# rev1_5.net
KiCad netlist of a schematic drawn in EAGLE
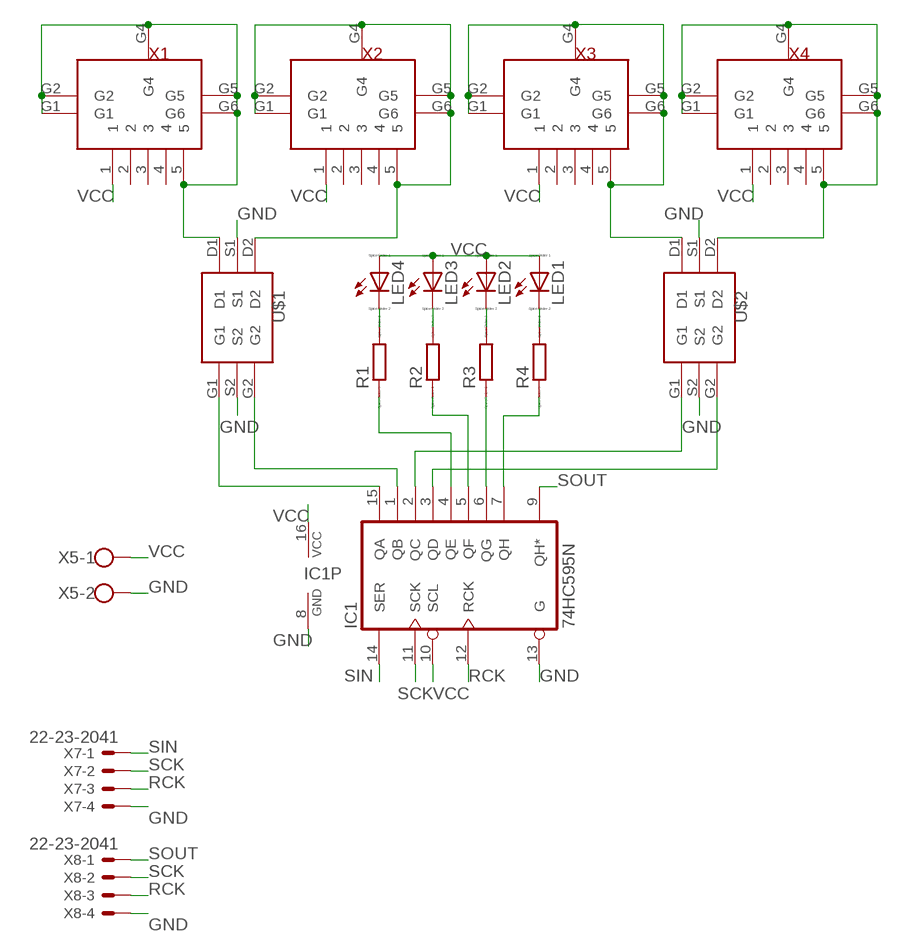
[diagram p0: schematic, sheet 1]

(export (version "E")
  (design (tool "Eeschema 10.0.6"))
  (components
    (comp (ref "IC1")
      (value "74HC595N")
      (footprint "eagle-import:DIL16")
      (libsource (lib "eagle-import") (part "74595NHC"))
    )
    (comp (ref "LED1")
      (value "LED_E")
      (footprint "eagle-import:LED_1206")
      (libsource (lib "eagle-import") (part "LED_E"))
    )
    (comp (ref "LED2")
      (value "LED_E")
      (footprint "eagle-import:LED_1206")
      (libsource (lib "eagle-import") (part "LED_E"))
    )
    (comp (ref "LED3")
      (value "LED_E")
      (footprint "eagle-import:LED_1206")
      (libsource (lib "eagle-import") (part "LED_E"))
    )
    (comp (ref "LED4")
      (value "LED_E")
      (footprint "eagle-import:LED_1206")
      (libsource (lib "eagle-import") (part "LED_E"))
    )
    (comp (ref "R1")
      (value "RR1005")
      (footprint "eagle-import:R1005")
      (libsource (lib "eagle-import") (part "RR1005"))
    )
    (comp (ref "R2")
      (value "RR1005")
      (footprint "eagle-import:R1005")
      (libsource (lib "eagle-import") (part "RR1005"))
    )
    (comp (ref "R3")
      (value "RR1005")
      (footprint "eagle-import:R1005")
      (libsource (lib "eagle-import") (part "RR1005"))
    )
    (comp (ref "R4")
      (value "RR1005")
      (footprint "eagle-import:R1005")
      (libsource (lib "eagle-import") (part "RR1005"))
    )
    (comp (ref "U$1")
      (value "FDC6305N")
      (footprint "eagle-import:FDC6305")
      (libsource (lib "eagle-import") (part "FDC6305N"))
    )
    (comp (ref "U$2")
      (value "FDC6305N")
      (footprint "eagle-import:FDC6305")
      (libsource (lib "eagle-import") (part "FDC6305N"))
    )
    (comp (ref "X1")
      (value "MUSBV")
      (footprint "eagle-import:MUSBV")
      (libsource (lib "eagle-import") (part "MUSBV"))
    )
    (comp (ref "X2")
      (value "MUSBV")
      (footprint "eagle-import:MUSBV")
      (libsource (lib "eagle-import") (part "MUSBV"))
    )
    (comp (ref "X3")
      (value "MUSBV")
      (footprint "eagle-import:MUSBV")
      (libsource (lib "eagle-import") (part "MUSBV"))
    )
    (comp (ref "X4")
      (value "MUSBV")
      (footprint "eagle-import:MUSBV")
      (libsource (lib "eagle-import") (part "MUSBV"))
    )
    (comp (ref "X5")
      (value "W237-102")
      (footprint "eagle-import:W237-102")
      (fields (field (name "MPN") "237-102"))
      (libsource (lib "eagle-import") (part "W237-102"))
    )
    (comp (ref "X7")
      (value "22-23-2041")
      (footprint "eagle-import:22-23-2041")
      (fields (field (name "MF") "MOLEX"))
      (libsource (lib "eagle-import") (part "22-23-2041"))
    )
    (comp (ref "X8")
      (value "22-23-2041")
      (footprint "eagle-import:22-23-2041")
      (fields (field (name "MF") "MOLEX"))
      (libsource (lib "eagle-import") (part "22-23-2041"))
    )
  )
  (nets
    (net (code "1") (name "/GND") (class "Default")
      (node (ref "IC1") (pin "13") (pinfunction "G_13") (pintype "input"))
      (node (ref "IC1") (pin "8") (pinfunction "GND_8") (pintype "power_in"))
      (node (ref "U$1") (pin "S1") (pinfunction "S1_S1") (pintype "bidirectional"))
      (node (ref "U$1") (pin "S2") (pinfunction "S2_S2") (pintype "bidirectional"))
      (node (ref "U$2") (pin "S1") (pinfunction "S1_S1") (pintype "bidirectional"))
      (node (ref "U$2") (pin "S2") (pinfunction "S2_S2") (pintype "bidirectional"))
      (node (ref "X5") (pin "2") (pinfunction "KL_2") (pintype "passive"))
      (node (ref "X7") (pin "4") (pinfunction "S_4") (pintype "passive"))
      (node (ref "X8") (pin "4") (pinfunction "S_4") (pintype "passive"))
    )
    (net (code "2") (name "/RCK") (class "Default")
      (node (ref "IC1") (pin "12") (pinfunction "RCK_12") (pintype "input"))
      (node (ref "X7") (pin "3") (pinfunction "S_3") (pintype "passive"))
      (node (ref "X8") (pin "3") (pinfunction "S_3") (pintype "passive"))
    )
    (net (code "3") (name "/SCK") (class "Default")
      (node (ref "IC1") (pin "11") (pinfunction "SCK_11") (pintype "input"))
      (node (ref "X7") (pin "2") (pinfunction "S_2") (pintype "passive"))
      (node (ref "X8") (pin "2") (pinfunction "S_2") (pintype "passive"))
    )
    (net (code "4") (name "/SIN") (class "Default")
      (node (ref "IC1") (pin "14") (pinfunction "SER_14") (pintype "input"))
      (node (ref "X7") (pin "1") (pinfunction "S_1") (pintype "passive"))
    )
    (net (code "5") (name "/SOUT") (class "Default")
      (node (ref "IC1") (pin "9") (pinfunction "QH*_9") (pintype "tri_state"))
      (node (ref "X8") (pin "1") (pinfunction "S_1") (pintype "passive"))
    )
    (net (code "6") (name "/VCC") (class "Default")
      (node (ref "IC1") (pin "10") (pinfunction "SCL_10") (pintype "input"))
      (node (ref "IC1") (pin "16") (pinfunction "VCC_16") (pintype "power_in"))
      (node (ref "LED1") (pin "A") (pinfunction "A_A") (pintype "passive"))
      (node (ref "LED2") (pin "A") (pinfunction "A_A") (pintype "passive"))
      (node (ref "LED3") (pin "A") (pinfunction "A_A") (pintype "passive"))
      (node (ref "LED4") (pin "A") (pinfunction "A_A") (pintype "passive"))
      (node (ref "X1") (pin "1") (pinfunction "1_1") (pintype "bidirectional"))
      (node (ref "X2") (pin "1") (pinfunction "1_1") (pintype "bidirectional"))
      (node (ref "X3") (pin "1") (pinfunction "1_1") (pintype "bidirectional"))
      (node (ref "X4") (pin "1") (pinfunction "1_1") (pintype "bidirectional"))
      (node (ref "X5") (pin "1") (pinfunction "KL_1") (pintype "passive"))
    )
    (net (code "7") (name "Net-(IC1A-QA)") (class "Default")
      (node (ref "IC1") (pin "15") (pinfunction "QA_15") (pintype "tri_state"))
      (node (ref "U$1") (pin "G1") (pinfunction "G1_G1") (pintype "bidirectional"))
    )
    (net (code "8") (name "Net-(IC1A-QB)") (class "Default")
      (node (ref "IC1") (pin "1") (pinfunction "QB_1") (pintype "tri_state"))
      (node (ref "U$1") (pin "G2") (pinfunction "G2_G2") (pintype "bidirectional"))
    )
    (net (code "9") (name "Net-(IC1A-QC)") (class "Default")
      (node (ref "IC1") (pin "2") (pinfunction "QC_2") (pintype "tri_state"))
      (node (ref "U$2") (pin "G1") (pinfunction "G1_G1") (pintype "bidirectional"))
    )
    (net (code "10") (name "Net-(IC1A-QD)") (class "Default")
      (node (ref "IC1") (pin "3") (pinfunction "QD_3") (pintype "tri_state"))
      (node (ref "U$2") (pin "G2") (pinfunction "G2_G2") (pintype "bidirectional"))
    )
    (net (code "11") (name "Net-(IC1A-QE)") (class "Default")
      (node (ref "IC1") (pin "4") (pinfunction "QE_4") (pintype "tri_state"))
      (node (ref "R1") (pin "1") (pinfunction "1_1") (pintype "passive"))
    )
    (net (code "12") (name "Net-(IC1A-QF)") (class "Default")
      (node (ref "IC1") (pin "5") (pinfunction "QF_5") (pintype "tri_state"))
      (node (ref "R2") (pin "1") (pinfunction "1_1") (pintype "passive"))
    )
    (net (code "13") (name "Net-(IC1A-QG)") (class "Default")
      (node (ref "IC1") (pin "6") (pinfunction "QG_6") (pintype "tri_state"))
      (node (ref "R3") (pin "1") (pinfunction "1_1") (pintype "passive"))
    )
    (net (code "14") (name "Net-(IC1A-QH)") (class "Default")
      (node (ref "IC1") (pin "7") (pinfunction "QH_7") (pintype "tri_state"))
      (node (ref "R4") (pin "1") (pinfunction "1_1") (pintype "passive"))
    )
    (net (code "15") (name "Net-(LED1-PadC)") (class "Default")
      (node (ref "LED1") (pin "C") (pinfunction "C_C") (pintype "passive"))
      (node (ref "R4") (pin "2") (pinfunction "2_2") (pintype "passive"))
    )
    (net (code "16") (name "Net-(LED2-PadC)") (class "Default")
      (node (ref "LED2") (pin "C") (pinfunction "C_C") (pintype "passive"))
      (node (ref "R3") (pin "2") (pinfunction "2_2") (pintype "passive"))
    )
    (net (code "17") (name "Net-(LED3-PadC)") (class "Default")
      (node (ref "LED3") (pin "C") (pinfunction "C_C") (pintype "passive"))
      (node (ref "R2") (pin "2") (pinfunction "2_2") (pintype "passive"))
    )
    (net (code "18") (name "Net-(LED4-PadC)") (class "Default")
      (node (ref "LED4") (pin "C") (pinfunction "C_C") (pintype "passive"))
      (node (ref "R1") (pin "2") (pinfunction "2_2") (pintype "passive"))
    )
    (net (code "19") (name "Net-(U$1-PadD1)") (class "Default")
      (node (ref "U$1") (pin "D1") (pinfunction "D1_D1") (pintype "bidirectional"))
      (node (ref "X1") (pin "5") (pinfunction "5_5") (pintype "bidirectional"))
      (node (ref "X1") (pin "G1") (pinfunction "G1_G1") (pintype "bidirectional"))
      (node (ref "X1") (pin "G2") (pinfunction "G2_G2") (pintype "bidirectional"))
      (node (ref "X1") (pin "G4") (pinfunction "G4_G4") (pintype "bidirectional"))
      (node (ref "X1") (pin "G5") (pinfunction "G5_G5") (pintype "bidirectional"))
      (node (ref "X1") (pin "G6") (pinfunction "G6_G6") (pintype "bidirectional"))
    )
    (net (code "20") (name "Net-(U$1-PadD2)") (class "Default")
      (node (ref "U$1") (pin "D2") (pinfunction "D2_D2") (pintype "bidirectional"))
      (node (ref "X2") (pin "5") (pinfunction "5_5") (pintype "bidirectional"))
      (node (ref "X2") (pin "G1") (pinfunction "G1_G1") (pintype "bidirectional"))
      (node (ref "X2") (pin "G2") (pinfunction "G2_G2") (pintype "bidirectional"))
      (node (ref "X2") (pin "G4") (pinfunction "G4_G4") (pintype "bidirectional"))
      (node (ref "X2") (pin "G5") (pinfunction "G5_G5") (pintype "bidirectional"))
      (node (ref "X2") (pin "G6") (pinfunction "G6_G6") (pintype "bidirectional"))
    )
    (net (code "21") (name "Net-(U$2-PadD1)") (class "Default")
      (node (ref "U$2") (pin "D1") (pinfunction "D1_D1") (pintype "bidirectional"))
      (node (ref "X3") (pin "5") (pinfunction "5_5") (pintype "bidirectional"))
      (node (ref "X3") (pin "G1") (pinfunction "G1_G1") (pintype "bidirectional"))
      (node (ref "X3") (pin "G2") (pinfunction "G2_G2") (pintype "bidirectional"))
      (node (ref "X3") (pin "G4") (pinfunction "G4_G4") (pintype "bidirectional"))
      (node (ref "X3") (pin "G5") (pinfunction "G5_G5") (pintype "bidirectional"))
      (node (ref "X3") (pin "G6") (pinfunction "G6_G6") (pintype "bidirectional"))
    )
    (net (code "22") (name "Net-(U$2-PadD2)") (class "Default")
      (node (ref "U$2") (pin "D2") (pinfunction "D2_D2") (pintype "bidirectional"))
      (node (ref "X4") (pin "5") (pinfunction "5_5") (pintype "bidirectional"))
      (node (ref "X4") (pin "G1") (pinfunction "G1_G1") (pintype "bidirectional"))
      (node (ref "X4") (pin "G2") (pinfunction "G2_G2") (pintype "bidirectional"))
      (node (ref "X4") (pin "G4") (pinfunction "G4_G4") (pintype "bidirectional"))
      (node (ref "X4") (pin "G5") (pinfunction "G5_G5") (pintype "bidirectional"))
      (node (ref "X4") (pin "G6") (pinfunction "G6_G6") (pintype "bidirectional"))
    )
    (net (code "23") (name "unconnected-(X1-Pad2)") (class "Default")
      (node (ref "X1") (pin "2") (pinfunction "2_2") (pintype "bidirectional"))
    )
    (net (code "24") (name "unconnected-(X1-Pad3)") (class "Default")
      (node (ref "X1") (pin "3") (pinfunction "3_3") (pintype "bidirectional"))
    )
    (net (code "25") (name "unconnected-(X1-Pad4)") (class "Default")
      (node (ref "X1") (pin "4") (pinfunction "4_4") (pintype "bidirectional"))
    )
    (net (code "26") (name "unconnected-(X2-Pad2)") (class "Default")
      (node (ref "X2") (pin "2") (pinfunction "2_2") (pintype "bidirectional"))
    )
    (net (code "27") (name "unconnected-(X2-Pad3)") (class "Default")
      (node (ref "X2") (pin "3") (pinfunction "3_3") (pintype "bidirectional"))
    )
    (net (code "28") (name "unconnected-(X2-Pad4)") (class "Default")
      (node (ref "X2") (pin "4") (pinfunction "4_4") (pintype "bidirectional"))
    )
    (net (code "29") (name "unconnected-(X3-Pad2)") (class "Default")
      (node (ref "X3") (pin "2") (pinfunction "2_2") (pintype "bidirectional"))
    )
    (net (code "30") (name "unconnected-(X3-Pad3)") (class "Default")
      (node (ref "X3") (pin "3") (pinfunction "3_3") (pintype "bidirectional"))
    )
    (net (code "31") (name "unconnected-(X3-Pad4)") (class "Default")
      (node (ref "X3") (pin "4") (pinfunction "4_4") (pintype "bidirectional"))
    )
    (net (code "32") (name "unconnected-(X4-Pad2)") (class "Default")
      (node (ref "X4") (pin "2") (pinfunction "2_2") (pintype "bidirectional"))
    )
    (net (code "33") (name "unconnected-(X4-Pad3)") (class "Default")
      (node (ref "X4") (pin "3") (pinfunction "3_3") (pintype "bidirectional"))
    )
    (net (code "34") (name "unconnected-(X4-Pad4)") (class "Default")
      (node (ref "X4") (pin "4") (pinfunction "4_4") (pintype "bidirectional"))
    )
  )
)
